# SH4_-_GIMBDRIVECONTROLS.net
KiCad netlist of a schematic drawn in Altium Designer
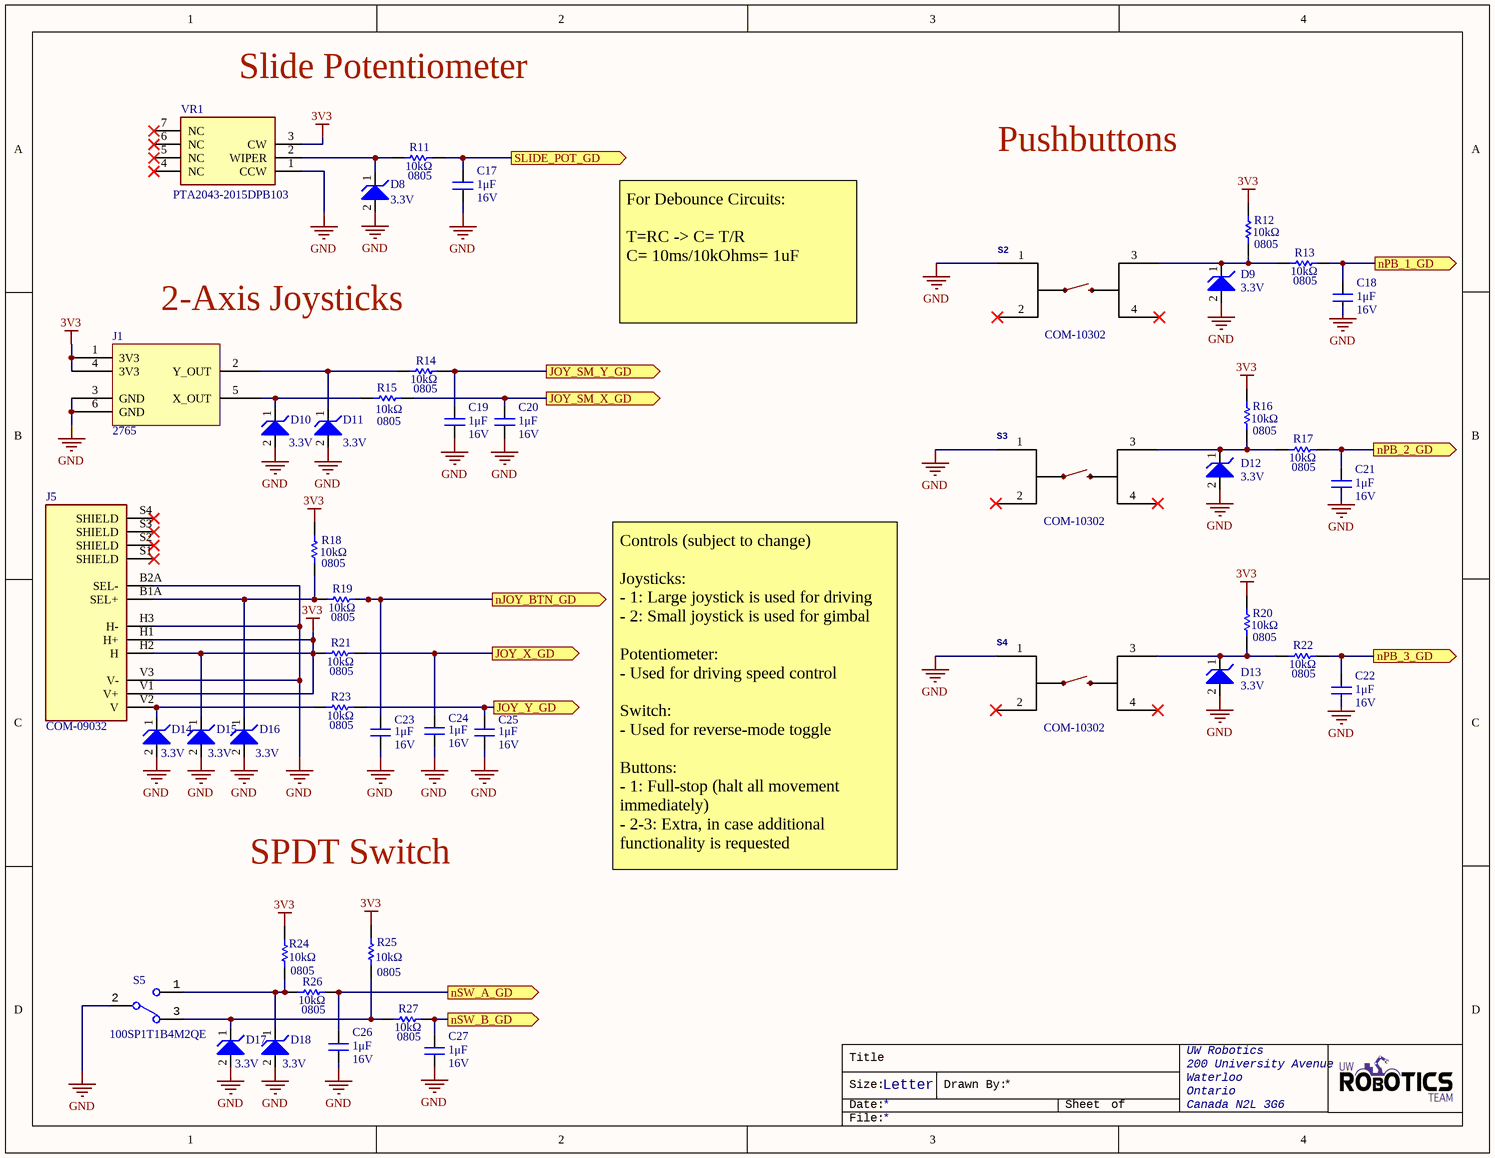
[diagram p0: SH4 - GIMBDRIVECONTROLS.SchDoc]

(export (version "E")
  (design (tool "Eeschema 10.0.6"))
  (components
    (comp (ref "C17")
      (value "1μF")
      (footprint "CAP2012")
      (description "CAP CER 1UF 16V X7R 0805")
      (fields
        (field (name "TOLERANCE") "10%")
        (field (name "VOLTAGE RATING") "16V")
        (field (name "Comment") "CAP_1uF_16V_0805")
      )
      (libsource (lib "UWRT_Schematic_Library_2020") (part "CAP_1uF_16V_0805"))
    )
    (comp (ref "C18")
      (value "1μF")
      (footprint "CAP2012")
      (description "CAP CER 1UF 16V X7R 0805")
      (fields
        (field (name "TOLERANCE") "10%")
        (field (name "VOLTAGE RATING") "16V")
        (field (name "Comment") "CAP_1uF_16V_0805")
      )
      (libsource (lib "UWRT_Schematic_Library_2020") (part "CAP_1uF_16V_0805"))
    )
    (comp (ref "C19")
      (value "1μF")
      (footprint "CAP2012")
      (description "CAP CER 1UF 16V X7R 0805")
      (fields
        (field (name "TOLERANCE") "10%")
        (field (name "VOLTAGE RATING") "16V")
        (field (name "Comment") "CAP_1uF_16V_0805")
      )
      (libsource (lib "UWRT_Schematic_Library_2020") (part "CAP_1uF_16V_0805"))
    )
    (comp (ref "C20")
      (value "1μF")
      (footprint "CAP2012")
      (description "CAP CER 1UF 16V X7R 0805")
      (fields
        (field (name "TOLERANCE") "10%")
        (field (name "VOLTAGE RATING") "16V")
        (field (name "Comment") "CAP_1uF_16V_0805")
      )
      (libsource (lib "UWRT_Schematic_Library_2020") (part "CAP_1uF_16V_0805"))
    )
    (comp (ref "C21")
      (value "1μF")
      (footprint "CAP2012")
      (description "CAP CER 1UF 16V X7R 0805")
      (fields
        (field (name "TOLERANCE") "10%")
        (field (name "VOLTAGE RATING") "16V")
        (field (name "Comment") "CAP_1uF_16V_0805")
      )
      (libsource (lib "UWRT_Schematic_Library_2020") (part "CAP_1uF_16V_0805"))
    )
    (comp (ref "C22")
      (value "1μF")
      (footprint "CAP2012")
      (description "CAP CER 1UF 16V X7R 0805")
      (fields
        (field (name "TOLERANCE") "10%")
        (field (name "VOLTAGE RATING") "16V")
        (field (name "Comment") "CAP_1uF_16V_0805")
      )
      (libsource (lib "UWRT_Schematic_Library_2020") (part "CAP_1uF_16V_0805"))
    )
    (comp (ref "C23")
      (value "1μF")
      (footprint "CAP2012")
      (description "CAP CER 1UF 16V X7R 0805")
      (fields
        (field (name "TOLERANCE") "10%")
        (field (name "VOLTAGE RATING") "16V")
        (field (name "Comment") "CAP_1uF_16V_0805")
      )
      (libsource (lib "UWRT_Schematic_Library_2020") (part "CAP_1uF_16V_0805"))
    )
    (comp (ref "C24")
      (value "1μF")
      (footprint "CAP2012")
      (description "CAP CER 1UF 16V X7R 0805")
      (fields
        (field (name "TOLERANCE") "10%")
        (field (name "VOLTAGE RATING") "16V")
        (field (name "Comment") "CAP_1uF_16V_0805")
      )
      (libsource (lib "UWRT_Schematic_Library_2020") (part "CAP_1uF_16V_0805"))
    )
    (comp (ref "C25")
      (value "1μF")
      (footprint "CAP2012")
      (description "CAP CER 1UF 16V X7R 0805")
      (fields
        (field (name "TOLERANCE") "10%")
        (field (name "VOLTAGE RATING") "16V")
        (field (name "Comment") "CAP_1uF_16V_0805")
      )
      (libsource (lib "UWRT_Schematic_Library_2020") (part "CAP_1uF_16V_0805"))
    )
    (comp (ref "C26")
      (value "1μF")
      (footprint "CAP2012")
      (description "CAP CER 1UF 16V X7R 0805")
      (fields
        (field (name "TOLERANCE") "10%")
        (field (name "VOLTAGE RATING") "16V")
        (field (name "Comment") "CAP_1uF_16V_0805")
      )
      (libsource (lib "UWRT_Schematic_Library_2020") (part "CAP_1uF_16V_0805"))
    )
    (comp (ref "C27")
      (value "1μF")
      (footprint "CAP2012")
      (description "CAP CER 1UF 16V X7R 0805")
      (fields
        (field (name "TOLERANCE") "10%")
        (field (name "VOLTAGE RATING") "16V")
        (field (name "Comment") "CAP_1uF_16V_0805")
      )
      (libsource (lib "UWRT_Schematic_Library_2020") (part "CAP_1uF_16V_0805"))
    )
    (comp (ref "D8")
      (value "TVS_DIODE_UNIDIR_3.3V")
      (footprint "SOD523")
      (description "TVS DIODE 3.3V 14.1V SOD523. Used to protect each connector input line going into the MCU.")
      (fields (field (name "REVERSE STANDOFF VOLTAGE") "3.3V"))
      (libsource (lib "UWRT_Schematic_Library_2020") (part "TVS_DIODE_UNIDIR_3.3V"))
    )
    (comp (ref "D9")
      (value "TVS_DIODE_UNIDIR_3.3V")
      (footprint "SOD523")
      (description "TVS DIODE 3.3V 14.1V SOD523. Used to protect each connector input line going into the MCU.")
      (fields (field (name "REVERSE STANDOFF VOLTAGE") "3.3V"))
      (libsource (lib "UWRT_Schematic_Library_2020") (part "TVS_DIODE_UNIDIR_3.3V"))
    )
    (comp (ref "D10")
      (value "TVS_DIODE_UNIDIR_3.3V")
      (footprint "SOD523")
      (description "TVS DIODE 3.3V 14.1V SOD523. Used to protect each connector input line going into the MCU.")
      (fields (field (name "REVERSE STANDOFF VOLTAGE") "3.3V"))
      (libsource (lib "UWRT_Schematic_Library_2020") (part "TVS_DIODE_UNIDIR_3.3V"))
    )
    (comp (ref "D11")
      (value "TVS_DIODE_UNIDIR_3.3V")
      (footprint "SOD523")
      (description "TVS DIODE 3.3V 14.1V SOD523. Used to protect each connector input line going into the MCU.")
      (fields (field (name "REVERSE STANDOFF VOLTAGE") "3.3V"))
      (libsource (lib "UWRT_Schematic_Library_2020") (part "TVS_DIODE_UNIDIR_3.3V"))
    )
    (comp (ref "D12")
      (value "TVS_DIODE_UNIDIR_3.3V")
      (footprint "SOD523")
      (description "TVS DIODE 3.3V 14.1V SOD523. Used to protect each connector input line going into the MCU.")
      (fields (field (name "REVERSE STANDOFF VOLTAGE") "3.3V"))
      (libsource (lib "UWRT_Schematic_Library_2020") (part "TVS_DIODE_UNIDIR_3.3V"))
    )
    (comp (ref "D13")
      (value "TVS_DIODE_UNIDIR_3.3V")
      (footprint "SOD523")
      (description "TVS DIODE 3.3V 14.1V SOD523. Used to protect each connector input line going into the MCU.")
      (fields (field (name "REVERSE STANDOFF VOLTAGE") "3.3V"))
      (libsource (lib "UWRT_Schematic_Library_2020") (part "TVS_DIODE_UNIDIR_3.3V"))
    )
    (comp (ref "D14")
      (value "TVS_DIODE_UNIDIR_3.3V")
      (footprint "SOD523")
      (description "TVS DIODE 3.3V 14.1V SOD523. Used to protect each connector input line going into the MCU.")
      (fields (field (name "REVERSE STANDOFF VOLTAGE") "3.3V"))
      (libsource (lib "UWRT_Schematic_Library_2020") (part "TVS_DIODE_UNIDIR_3.3V"))
    )
    (comp (ref "D15")
      (value "TVS_DIODE_UNIDIR_3.3V")
      (footprint "SOD523")
      (description "TVS DIODE 3.3V 14.1V SOD523. Used to protect each connector input line going into the MCU.")
      (fields (field (name "REVERSE STANDOFF VOLTAGE") "3.3V"))
      (libsource (lib "UWRT_Schematic_Library_2020") (part "TVS_DIODE_UNIDIR_3.3V"))
    )
    (comp (ref "D16")
      (value "TVS_DIODE_UNIDIR_3.3V")
      (footprint "SOD523")
      (description "TVS DIODE 3.3V 14.1V SOD523. Used to protect each connector input line going into the MCU.")
      (fields (field (name "REVERSE STANDOFF VOLTAGE") "3.3V"))
      (libsource (lib "UWRT_Schematic_Library_2020") (part "TVS_DIODE_UNIDIR_3.3V"))
    )
    (comp (ref "D17")
      (value "TVS_DIODE_UNIDIR_3.3V")
      (footprint "SOD523")
      (description "TVS DIODE 3.3V 14.1V SOD523. Used to protect each connector input line going into the MCU.")
      (fields (field (name "REVERSE STANDOFF VOLTAGE") "3.3V"))
      (libsource (lib "UWRT_Schematic_Library_2020") (part "TVS_DIODE_UNIDIR_3.3V"))
    )
    (comp (ref "D18")
      (value "TVS_DIODE_UNIDIR_3.3V")
      (footprint "SOD523")
      (description "TVS DIODE 3.3V 14.1V SOD523. Used to protect each connector input line going into the MCU.")
      (fields (field (name "REVERSE STANDOFF VOLTAGE") "3.3V"))
      (libsource (lib "UWRT_Schematic_Library_2020") (part "TVS_DIODE_UNIDIR_3.3V"))
    )
    (comp (ref "J1")
      (value "2_AXIS_JOYSTICK_SMALL")
      (footprint "2_AXIS_JOYSTICK_SMALL")
      (description "JOYSTICK 10K OHM 2 AXIS TH")
      (fields (field (name "MANUFACTURER PART NUMBER 1") "2765"))
      (libsource (lib "UWRT_Schematic_Library_2020") (part "2_AXIS_JOYSTICK_SMALL"))
    )
    (comp (ref "J5")
      (value "2_AXIS_JOYSTICK")
      (footprint "2_AXIS_JOYSTICK")
      (description "JOYSTICK 10K OHM 2 AXIS TH")
      (fields (field (name "MANUFACTURER PART NUMBER 1") "COM-09032"))
      (libsource (lib "UWRT_Schematic_Library_2020") (part "2_AXIS_JOYSTICK"))
    )
    (comp (ref "R11")
      (value "10kΩ")
      (footprint "RESC0805")
      (description "RES 10K OHM 5% 1/8W 0805")
      (fields (field (name "CASE CODE (IMPERIAL)") "0805") (field (name "Comment") "RES_10kΩ_0805_5%"))
      (libsource (lib "UWRT_Schematic_Library_2020") (part "RES_10kΩ_0805_5%"))
    )
    (comp (ref "R12")
      (value "10kΩ")
      (footprint "RESC0805")
      (description "RES 10K OHM 5% 1/8W 0805")
      (fields (field (name "CASE CODE (IMPERIAL)") "0805") (field (name "Comment") "RES_10kΩ_0805_5%"))
      (libsource (lib "UWRT_Schematic_Library_2020") (part "RES_10kΩ_0805_5%"))
    )
    (comp (ref "R13")
      (value "10kΩ")
      (footprint "RESC0805")
      (description "RES 10K OHM 5% 1/8W 0805")
      (fields (field (name "CASE CODE (IMPERIAL)") "0805") (field (name "Comment") "RES_10kΩ_0805_5%"))
      (libsource (lib "UWRT_Schematic_Library_2020") (part "RES_10kΩ_0805_5%"))
    )
    (comp (ref "R14")
      (value "10kΩ")
      (footprint "RESC0805")
      (description "RES 10K OHM 5% 1/8W 0805")
      (fields (field (name "CASE CODE (IMPERIAL)") "0805") (field (name "Comment") "RES_10kΩ_0805_5%"))
      (libsource (lib "UWRT_Schematic_Library_2020") (part "RES_10kΩ_0805_5%"))
    )
    (comp (ref "R15")
      (value "10kΩ")
      (footprint "RESC0805")
      (description "RES 10K OHM 5% 1/8W 0805")
      (fields (field (name "CASE CODE (IMPERIAL)") "0805") (field (name "Comment") "RES_10kΩ_0805_5%"))
      (libsource (lib "UWRT_Schematic_Library_2020") (part "RES_10kΩ_0805_5%"))
    )
    (comp (ref "R16")
      (value "10kΩ")
      (footprint "RESC0805")
      (description "RES 10K OHM 5% 1/8W 0805")
      (fields (field (name "CASE CODE (IMPERIAL)") "0805") (field (name "Comment") "RES_10kΩ_0805_5%"))
      (libsource (lib "UWRT_Schematic_Library_2020") (part "RES_10kΩ_0805_5%"))
    )
    (comp (ref "R17")
      (value "10kΩ")
      (footprint "RESC0805")
      (description "RES 10K OHM 5% 1/8W 0805")
      (fields (field (name "CASE CODE (IMPERIAL)") "0805") (field (name "Comment") "RES_10kΩ_0805_5%"))
      (libsource (lib "UWRT_Schematic_Library_2020") (part "RES_10kΩ_0805_5%"))
    )
    (comp (ref "R18")
      (value "10kΩ")
      (footprint "RESC0805")
      (description "RES 10K OHM 5% 1/8W 0805")
      (fields (field (name "CASE CODE (IMPERIAL)") "0805") (field (name "Comment") "RES_10kΩ_0805_5%"))
      (libsource (lib "UWRT_Schematic_Library_2020") (part "RES_10kΩ_0805_5%"))
    )
    (comp (ref "R19")
      (value "10kΩ")
      (footprint "RESC0805")
      (description "RES 10K OHM 5% 1/8W 0805")
      (fields (field (name "CASE CODE (IMPERIAL)") "0805") (field (name "Comment") "RES_10kΩ_0805_5%"))
      (libsource (lib "UWRT_Schematic_Library_2020") (part "RES_10kΩ_0805_5%"))
    )
    (comp (ref "R20")
      (value "10kΩ")
      (footprint "RESC0805")
      (description "RES 10K OHM 5% 1/8W 0805")
      (fields (field (name "CASE CODE (IMPERIAL)") "0805") (field (name "Comment") "RES_10kΩ_0805_5%"))
      (libsource (lib "UWRT_Schematic_Library_2020") (part "RES_10kΩ_0805_5%"))
    )
    (comp (ref "R21")
      (value "10kΩ")
      (footprint "RESC0805")
      (description "RES 10K OHM 5% 1/8W 0805")
      (fields (field (name "CASE CODE (IMPERIAL)") "0805") (field (name "Comment") "RES_10kΩ_0805_5%"))
      (libsource (lib "UWRT_Schematic_Library_2020") (part "RES_10kΩ_0805_5%"))
    )
    (comp (ref "R22")
      (value "10kΩ")
      (footprint "RESC0805")
      (description "RES 10K OHM 5% 1/8W 0805")
      (fields (field (name "CASE CODE (IMPERIAL)") "0805") (field (name "Comment") "RES_10kΩ_0805_5%"))
      (libsource (lib "UWRT_Schematic_Library_2020") (part "RES_10kΩ_0805_5%"))
    )
    (comp (ref "R23")
      (value "10kΩ")
      (footprint "RESC0805")
      (description "RES 10K OHM 5% 1/8W 0805")
      (fields (field (name "CASE CODE (IMPERIAL)") "0805") (field (name "Comment") "RES_10kΩ_0805_5%"))
      (libsource (lib "UWRT_Schematic_Library_2020") (part "RES_10kΩ_0805_5%"))
    )
    (comp (ref "R24")
      (value "10kΩ")
      (footprint "RESC0805")
      (description "RES 10K OHM 5% 1/8W 0805")
      (fields (field (name "CASE CODE (IMPERIAL)") "0805") (field (name "Comment") "RES_10kΩ_0805_5%"))
      (libsource (lib "UWRT_Schematic_Library_2020") (part "RES_10kΩ_0805_5%"))
    )
    (comp (ref "R25")
      (value "10kΩ")
      (footprint "RESC0805")
      (description "RES 10K OHM 5% 1/8W 0805")
      (fields (field (name "CASE CODE (IMPERIAL)") "0805") (field (name "Comment") "RES_10kΩ_0805_5%"))
      (libsource (lib "UWRT_Schematic_Library_2020") (part "RES_10kΩ_0805_5%"))
    )
    (comp (ref "R26")
      (value "10kΩ")
      (footprint "RESC0805")
      (description "RES 10K OHM 5% 1/8W 0805")
      (fields (field (name "CASE CODE (IMPERIAL)") "0805") (field (name "Comment") "RES_10kΩ_0805_5%"))
      (libsource (lib "UWRT_Schematic_Library_2020") (part "RES_10kΩ_0805_5%"))
    )
    (comp (ref "R27")
      (value "10kΩ")
      (footprint "RESC0805")
      (description "RES 10K OHM 5% 1/8W 0805")
      (fields (field (name "CASE CODE (IMPERIAL)") "0805") (field (name "Comment") "RES_10kΩ_0805_5%"))
      (libsource (lib "UWRT_Schematic_Library_2020") (part "RES_10kΩ_0805_5%"))
    )
    (comp (ref "S2")
      (value "Pushbutton")
      (footprint "TACTILE_SWITCH_PTH_12MM")
      (description "Momentary Switch (Pushbutton) - SPST")
      (fields (field (name "MANUFACTURER PART NUMBER 1") "COM-10302"))
      (libsource (lib "UWRT_Schematic_Library_2020") (part "MOMENTARY_SWITCH_TH"))
    )
    (comp (ref "S3")
      (value "Pushbutton")
      (footprint "TACTILE_SWITCH_PTH_12MM")
      (description "Momentary Switch (Pushbutton) - SPST")
      (fields (field (name "MANUFACTURER PART NUMBER 1") "COM-10302"))
      (libsource (lib "UWRT_Schematic_Library_2020") (part "MOMENTARY_SWITCH_TH"))
    )
    (comp (ref "S4")
      (value "Pushbutton")
      (footprint "TACTILE_SWITCH_PTH_12MM")
      (description "Momentary Switch (Pushbutton) - SPST")
      (fields (field (name "MANUFACTURER PART NUMBER 1") "COM-10302"))
      (libsource (lib "UWRT_Schematic_Library_2020") (part "MOMENTARY_SWITCH_TH"))
    )
    (comp (ref "S5")
      (value "SW_SPDT")
      (footprint "100SP1T1B4M2QE")
      (description "SWITCH TOGGLE SPDT 5A 120V")
      (fields (field (name "MANUFACTURER PART NUMBER 1") "100SP1T1B4M2QE"))
      (libsource (lib "UWRT_Schematic_Library_2020") (part "SW_SPDT"))
    )
    (comp (ref "VR1")
      (value "POT_10K_SLIDE")
      (footprint "PTA20432015CPB103")
      (description "SLIDE POT 10K OHM 0.1W TOP 20MM")
      (fields
        (field (name "MANUFACTURER PART NUMBER 1") "PTA2043-2015DPB103")
        (field (name "TOLERANCE") "20%")
      )
      (libsource (lib "UWRT_Schematic_Library_2020") (part "POT_10K_SLIDE"))
    )
  )
  (nets
    (net (code "1") (name "/JOY_SM_X_GD") (class "Default")
      (node (ref "C20") (pin "2") (pinfunction "2_2") (pintype "passive"))
      (node (ref "R15") (pin "2") (pinfunction "2_2") (pintype "passive"))
    )
    (net (code "2") (name "/JOY_SM_Y_GD") (class "Default")
      (node (ref "C19") (pin "2") (pinfunction "2_2") (pintype "passive"))
      (node (ref "R14") (pin "2") (pinfunction "2_2") (pintype "passive"))
    )
    (net (code "3") (name "/JOY_X_GD") (class "Default")
      (node (ref "C24") (pin "2") (pinfunction "2_2") (pintype "passive"))
      (node (ref "R21") (pin "2") (pinfunction "2_2") (pintype "passive"))
    )
    (net (code "4") (name "/JOY_Y_GD") (class "Default")
      (node (ref "C25") (pin "2") (pinfunction "2_2") (pintype "passive"))
      (node (ref "R23") (pin "2") (pinfunction "2_2") (pintype "passive"))
    )
    (net (code "5") (name "/SLIDE_POT_GD") (class "Default")
      (node (ref "C17") (pin "2") (pinfunction "2_2") (pintype "passive"))
      (node (ref "R11") (pin "2") (pinfunction "2_2") (pintype "passive"))
    )
    (net (code "6") (name "/nJOY_BTN_GD") (class "Default")
      (node (ref "C23") (pin "2") (pinfunction "2_2") (pintype "passive"))
      (node (ref "R19") (pin "2") (pinfunction "2_2") (pintype "passive"))
    )
    (net (code "7") (name "/nPB_1_GD") (class "Default")
      (node (ref "C18") (pin "2") (pinfunction "2_2") (pintype "passive"))
      (node (ref "R13") (pin "2") (pinfunction "2_2") (pintype "passive"))
    )
    (net (code "8") (name "/nPB_2_GD") (class "Default")
      (node (ref "C21") (pin "2") (pinfunction "2_2") (pintype "passive"))
      (node (ref "R17") (pin "2") (pinfunction "2_2") (pintype "passive"))
    )
    (net (code "9") (name "/nPB_3_GD") (class "Default")
      (node (ref "C22") (pin "2") (pinfunction "2_2") (pintype "passive"))
      (node (ref "R22") (pin "2") (pinfunction "2_2") (pintype "passive"))
    )
    (net (code "10") (name "/nSW_A_GD") (class "Default")
      (node (ref "C26") (pin "2") (pinfunction "2_2") (pintype "passive"))
      (node (ref "R26") (pin "2") (pinfunction "2_2") (pintype "passive"))
    )
    (net (code "11") (name "/nSW_B_GD") (class "Default")
      (node (ref "C27") (pin "2") (pinfunction "2_2") (pintype "passive"))
      (node (ref "R27") (pin "2") (pinfunction "2_2") (pintype "passive"))
    )
    (net (code "12") (name "3V3") (class "Default")
      (node (ref "D15") (pin "1") (pinfunction "1_1") (pintype "passive"))
      (node (ref "J1") (pin "1") (pinfunction "3V3_1") (pintype "passive"))
      (node (ref "J1") (pin "4") (pinfunction "3V3_4") (pintype "passive"))
      (node (ref "J5") (pin "H1") (pinfunction "H+_H1") (pintype "passive"))
      (node (ref "J5") (pin "H2") (pinfunction "H_H2") (pintype "passive"))
      (node (ref "J5") (pin "V1") (pinfunction "V+_V1") (pintype "passive"))
      (node (ref "R12") (pin "1") (pinfunction "1_1") (pintype "passive"))
      (node (ref "R16") (pin "1") (pinfunction "1_1") (pintype "passive"))
      (node (ref "R18") (pin "1") (pinfunction "1_1") (pintype "passive"))
      (node (ref "R20") (pin "1") (pinfunction "1_1") (pintype "passive"))
      (node (ref "R21") (pin "1") (pinfunction "1_1") (pintype "passive"))
      (node (ref "R24") (pin "1") (pinfunction "1_1") (pintype "passive"))
      (node (ref "R25") (pin "1") (pinfunction "1_1") (pintype "passive"))
      (node (ref "VR1") (pin "3") (pinfunction "CW_3") (pintype "passive"))
    )
    (net (code "13") (name "GND") (class "Default")
      (node (ref "C17") (pin "1") (pinfunction "1_1") (pintype "passive"))
      (node (ref "C18") (pin "1") (pinfunction "1_1") (pintype "passive"))
      (node (ref "C19") (pin "1") (pinfunction "1_1") (pintype "passive"))
      (node (ref "C20") (pin "1") (pinfunction "1_1") (pintype "passive"))
      (node (ref "C21") (pin "1") (pinfunction "1_1") (pintype "passive"))
      (node (ref "C22") (pin "1") (pinfunction "1_1") (pintype "passive"))
      (node (ref "C23") (pin "1") (pinfunction "1_1") (pintype "passive"))
      (node (ref "C24") (pin "1") (pinfunction "1_1") (pintype "passive"))
      (node (ref "C25") (pin "1") (pinfunction "1_1") (pintype "passive"))
      (node (ref "C26") (pin "1") (pinfunction "1_1") (pintype "passive"))
      (node (ref "C27") (pin "1") (pinfunction "1_1") (pintype "passive"))
      (node (ref "D10") (pin "2") (pinfunction "2_2") (pintype "passive"))
      (node (ref "D11") (pin "2") (pinfunction "2_2") (pintype "passive"))
      (node (ref "D12") (pin "2") (pinfunction "2_2") (pintype "passive"))
      (node (ref "D13") (pin "2") (pinfunction "2_2") (pintype "passive"))
      (node (ref "D14") (pin "2") (pinfunction "2_2") (pintype "passive"))
      (node (ref "D15") (pin "2") (pinfunction "2_2") (pintype "passive"))
      (node (ref "D16") (pin "2") (pinfunction "2_2") (pintype "passive"))
      (node (ref "D17") (pin "2") (pinfunction "2_2") (pintype "passive"))
      (node (ref "D18") (pin "2") (pinfunction "2_2") (pintype "passive"))
      (node (ref "D8") (pin "2") (pinfunction "2_2") (pintype "passive"))
      (node (ref "D9") (pin "2") (pinfunction "2_2") (pintype "passive"))
      (node (ref "J1") (pin "3") (pinfunction "GND_3") (pintype "passive"))
      (node (ref "J1") (pin "6") (pinfunction "GND_6") (pintype "passive"))
      (node (ref "J5") (pin "B2A") (pinfunction "SEL-_B2A") (pintype "passive"))
      (node (ref "J5") (pin "H3") (pinfunction "H-_H3") (pintype "passive"))
      (node (ref "J5") (pin "V3") (pinfunction "V-_V3") (pintype "passive"))
      (node (ref "S2") (pin "1") (pinfunction "1_1") (pintype "passive"))
      (node (ref "S3") (pin "1") (pinfunction "1_1") (pintype "passive"))
      (node (ref "S4") (pin "1") (pinfunction "1_1") (pintype "passive"))
      (node (ref "S5") (pin "2") (pinfunction "2_2") (pintype "passive"))
      (node (ref "VR1") (pin "1") (pinfunction "CCW_1") (pintype "passive"))
    )
    (net (code "14") (name "Net-(D9-Pad1)") (class "Default")
      (node (ref "D9") (pin "1") (pinfunction "1_1") (pintype "passive"))
      (node (ref "R12") (pin "2") (pinfunction "2_2") (pintype "passive"))
      (node (ref "R13") (pin "1") (pinfunction "1_1") (pintype "passive"))
      (node (ref "S2") (pin "3") (pinfunction "3_3") (pintype "passive"))
    )
    (net (code "15") (name "Net-(D12-Pad1)") (class "Default")
      (node (ref "D12") (pin "1") (pinfunction "1_1") (pintype "passive"))
      (node (ref "R16") (pin "2") (pinfunction "2_2") (pintype "passive"))
      (node (ref "R17") (pin "1") (pinfunction "1_1") (pintype "passive"))
      (node (ref "S3") (pin "3") (pinfunction "3_3") (pintype "passive"))
    )
    (net (code "16") (name "Net-(D13-Pad1)") (class "Default")
      (node (ref "D13") (pin "1") (pinfunction "1_1") (pintype "passive"))
      (node (ref "R20") (pin "2") (pinfunction "2_2") (pintype "passive"))
      (node (ref "R22") (pin "1") (pinfunction "1_1") (pintype "passive"))
      (node (ref "S4") (pin "3") (pinfunction "3_3") (pintype "passive"))
    )
    (net (code "17") (name "Net-(D17-Pad1)") (class "Default")
      (node (ref "D17") (pin "1") (pinfunction "1_1") (pintype "passive"))
      (node (ref "R25") (pin "2") (pinfunction "2_2") (pintype "passive"))
      (node (ref "R27") (pin "1") (pinfunction "1_1") (pintype "passive"))
      (node (ref "S5") (pin "3") (pinfunction "3_3") (pintype "passive"))
    )
    (net (code "18") (name "Net-(D18-Pad1)") (class "Default")
      (node (ref "D18") (pin "1") (pinfunction "1_1") (pintype "passive"))
      (node (ref "R24") (pin "2") (pinfunction "2_2") (pintype "passive"))
      (node (ref "R26") (pin "1") (pinfunction "1_1") (pintype "passive"))
      (node (ref "S5") (pin "1") (pinfunction "1_1") (pintype "passive"))
    )
    (net (code "19") (name "Net-(J1-X_OUT)") (class "Default")
      (node (ref "D10") (pin "1") (pinfunction "1_1") (pintype "passive"))
      (node (ref "J1") (pin "5") (pinfunction "X_OUT_5") (pintype "passive"))
      (node (ref "R15") (pin "1") (pinfunction "1_1") (pintype "passive"))
    )
    (net (code "20") (name "Net-(J1-Y_OUT)") (class "Default")
      (node (ref "D11") (pin "1") (pinfunction "1_1") (pintype "passive"))
      (node (ref "J1") (pin "2") (pinfunction "Y_OUT_2") (pintype "passive"))
      (node (ref "R14") (pin "1") (pinfunction "1_1") (pintype "passive"))
    )
    (net (code "21") (name "Net-(J5-SEL+)") (class "Default")
      (node (ref "D16") (pin "1") (pinfunction "1_1") (pintype "passive"))
      (node (ref "J5") (pin "B1A") (pinfunction "SEL+_B1A") (pintype "passive"))
      (node (ref "R18") (pin "2") (pinfunction "2_2") (pintype "passive"))
      (node (ref "R19") (pin "1") (pinfunction "1_1") (pintype "passive"))
    )
    (net (code "22") (name "Net-(J5-V)") (class "Default")
      (node (ref "D14") (pin "1") (pinfunction "1_1") (pintype "passive"))
      (node (ref "J5") (pin "V2") (pinfunction "V_V2") (pintype "passive"))
      (node (ref "R23") (pin "1") (pinfunction "1_1") (pintype "passive"))
    )
    (net (code "23") (name "Net-(VR1-WIPER)") (class "Default")
      (node (ref "D8") (pin "1") (pinfunction "1_1") (pintype "passive"))
      (node (ref "R11") (pin "1") (pinfunction "1_1") (pintype "passive"))
      (node (ref "VR1") (pin "2") (pinfunction "WIPER_2") (pintype "passive"))
    )
    (net (code "24") (name "unconnected-(J5-SHIELD-PadS1)") (class "Default")
      (node (ref "J5") (pin "S1") (pinfunction "SHIELD_S1") (pintype "passive+no_connect"))
    )
    (net (code "25") (name "unconnected-(J5-SHIELD-PadS2)") (class "Default")
      (node (ref "J5") (pin "S2") (pinfunction "SHIELD_S2") (pintype "passive+no_connect"))
    )
    (net (code "26") (name "unconnected-(J5-SHIELD-PadS3)") (class "Default")
      (node (ref "J5") (pin "S3") (pinfunction "SHIELD_S3") (pintype "passive+no_connect"))
    )
    (net (code "27") (name "unconnected-(J5-SHIELD-PadS4)") (class "Default")
      (node (ref "J5") (pin "S4") (pinfunction "SHIELD_S4") (pintype "passive+no_connect"))
    )
    (net (code "28") (name "unconnected-(S2-Pad2)") (class "Default")
      (node (ref "S2") (pin "2") (pinfunction "2_2") (pintype "passive+no_connect"))
    )
    (net (code "29") (name "unconnected-(S2-Pad4)") (class "Default")
      (node (ref "S2") (pin "4") (pinfunction "4_4") (pintype "passive+no_connect"))
    )
    (net (code "30") (name "unconnected-(S3-Pad2)") (class "Default")
      (node (ref "S3") (pin "2") (pinfunction "2_2") (pintype "passive+no_connect"))
    )
    (net (code "31") (name "unconnected-(S3-Pad4)") (class "Default")
      (node (ref "S3") (pin "4") (pinfunction "4_4") (pintype "passive+no_connect"))
    )
    (net (code "32") (name "unconnected-(S4-Pad2)") (class "Default")
      (node (ref "S4") (pin "2") (pinfunction "2_2") (pintype "passive+no_connect"))
    )
    (net (code "33") (name "unconnected-(S4-Pad4)") (class "Default")
      (node (ref "S4") (pin "4") (pinfunction "4_4") (pintype "passive+no_connect"))
    )
    (net (code "34") (name "unconnected-(VR1-NC-Pad4)") (class "Default")
      (node (ref "VR1") (pin "4") (pinfunction "NC_4") (pintype "passive+no_connect"))
    )
    (net (code "35") (name "unconnected-(VR1-NC-Pad5)") (class "Default")
      (node (ref "VR1") (pin "5") (pinfunction "NC_5") (pintype "passive+no_connect"))
    )
    (net (code "36") (name "unconnected-(VR1-NC-Pad6)") (class "Default")
      (node (ref "VR1") (pin "6") (pinfunction "NC_6") (pintype "passive+no_connect"))
    )
    (net (code "37") (name "unconnected-(VR1-NC-Pad7)") (class "Default")
      (node (ref "VR1") (pin "7") (pinfunction "NC_7") (pintype "passive+no_connect"))
    )
  )
)
